# SD_Card.net
KiCad netlist of a schematic drawn in Altium Designer
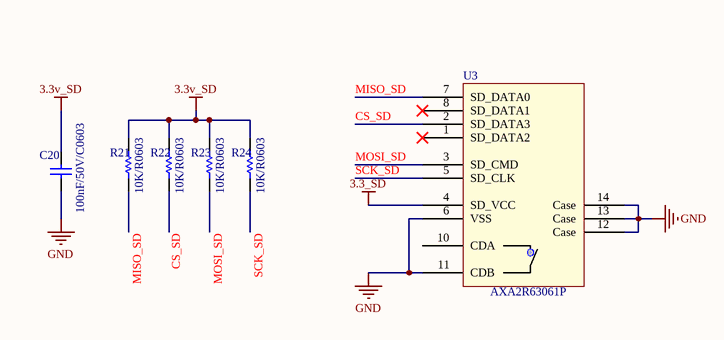
[diagram p0: SD Card.SchDoc]

(export (version "E")
  (design (tool "Eeschema 10.0.6"))
  (components
    (comp (ref "C20")
      (value "100nF/50V/C0603")
      (footprint "Manh_Capacitor:C0603")
      (description "CAP CER 0.1UF 50V 10% X7R 0603")
      (fields
        (field (name "MANUFACTURER") "Murata Electronics North America")
        (field (name "MANUFACTURER PART NUMBER") "GRM188R71H104KA93D")
      )
      (libsource (lib "Manh_Capacitor") (part "0.1uF/50V/C0603/10%"))
    )
    (comp (ref "R21")
      (value "10K/R0603")
      (footprint "Manh_Resistor:R0603")
      (description "RES SMD 10K OHM 1% 1/10W 0603")
      (fields
        (field (name "MANUFACTURER") "Yageo")
        (field (name "MANUFACTURER PART NUMBER") "RC0603FR-0710KL")
      )
      (libsource (lib "Manh_Resistor") (part "10K/R0603/1%"))
    )
    (comp (ref "R22")
      (value "10K/R0603")
      (footprint "Manh_Resistor:R0603")
      (description "RES SMD 10K OHM 1% 1/10W 0603")
      (fields
        (field (name "MANUFACTURER") "Yageo")
        (field (name "MANUFACTURER PART NUMBER") "RC0603FR-0710KL")
      )
      (libsource (lib "Manh_Resistor") (part "10K/R0603/1%"))
    )
    (comp (ref "R23")
      (value "10K/R0603")
      (footprint "Manh_Resistor:R0603")
      (description "RES SMD 10K OHM 1% 1/10W 0603")
      (fields
        (field (name "MANUFACTURER") "Yageo")
        (field (name "MANUFACTURER PART NUMBER") "RC0603FR-0710KL")
      )
      (libsource (lib "Manh_Resistor") (part "10K/R0603/1%"))
    )
    (comp (ref "R24")
      (value "10K/R0603")
      (footprint "Manh_Resistor:R0603")
      (description "RES SMD 10K OHM 1% 1/10W 0603")
      (fields
        (field (name "MANUFACTURER") "Yageo")
        (field (name "MANUFACTURER PART NUMBER") "RC0603FR-0710KL")
      )
      (libsource (lib "Manh_Resistor") (part "10K/R0603/1%"))
    )
    (comp (ref "U3")
      (value "AXA2R63061P")
      (footprint "Manh_Miscellaneous:mini SD card - T-flash")
      (description "CONN SD CARD PUSH-PUSH R/A SMD")
      (fields (field (name "MANUFACTURER") "Panasonic Electric Works"))
      (libsource (lib "Manh_Miscellaneous") (part "MICRO SD CARD P-P R/A SMD"))
    )
  )
  (nets
    (net (code "1") (name "/CS_SD") (class "Default")
      (node (ref "U3") (pin "2") (pinfunction "SD_DATA3_2") (pintype "passive"))
    )
    (net (code "2") (name "/MISO_SD") (class "Default")
      (node (ref "R21") (pin "1") (pinfunction "1_1") (pintype "passive"))
      (node (ref "U3") (pin "7") (pinfunction "SD_DATA0_7") (pintype "passive"))
    )
    (net (code "3") (name "/MOSI_SD") (class "Default")
      (node (ref "R23") (pin "1") (pinfunction "1_1") (pintype "passive"))
      (node (ref "U3") (pin "3") (pinfunction "SD_CMD_3") (pintype "passive"))
    )
    (net (code "4") (name "/SCK_SD") (class "Default")
      (node (ref "R24") (pin "1") (pinfunction "1_1") (pintype "passive"))
      (node (ref "U3") (pin "5") (pinfunction "SD_CLK_5") (pintype "passive"))
    )
    (net (code "5") (name "3.3_SD") (class "Default")
      (node (ref "U3") (pin "4") (pinfunction "SD_VCC_4") (pintype "passive"))
    )
    (net (code "6") (name "3.3v_SD") (class "Default")
      (node (ref "C20") (pin "2") (pinfunction "2_2") (pintype "passive"))
      (node (ref "R21") (pin "2") (pinfunction "2_2") (pintype "passive"))
      (node (ref "R22") (pin "2") (pinfunction "2_2") (pintype "passive"))
      (node (ref "R23") (pin "2") (pinfunction "2_2") (pintype "passive"))
      (node (ref "R24") (pin "2") (pinfunction "2_2") (pintype "passive"))
    )
    (net (code "7") (name "GND") (class "Default")
      (node (ref "C20") (pin "1") (pinfunction "1_1") (pintype "passive"))
      (node (ref "U3") (pin "11") (pinfunction "CDB_11") (pintype "passive"))
      (node (ref "U3") (pin "12") (pinfunction "Case_12") (pintype "passive"))
      (node (ref "U3") (pin "13") (pinfunction "Case_13") (pintype "passive"))
      (node (ref "U3") (pin "14") (pinfunction "Case_14") (pintype "passive"))
      (node (ref "U3") (pin "6") (pinfunction "VSS_6") (pintype "passive"))
    )
    (net (code "8") (name "unconnected-(R22-Pad1)") (class "Default")
      (node (ref "R22") (pin "1") (pinfunction "1_1") (pintype "passive"))
    )
    (net (code "9") (name "unconnected-(U3-CDA-Pad10)") (class "Default")
      (node (ref "U3") (pin "10") (pinfunction "CDA_10") (pintype "passive"))
    )
    (net (code "10") (name "unconnected-(U3-SD_DATA1-Pad8)") (class "Default")
      (node (ref "U3") (pin "8") (pinfunction "SD_DATA1_8") (pintype "passive+no_connect"))
    )
    (net (code "11") (name "unconnected-(U3-SD_DATA2-Pad1)") (class "Default")
      (node (ref "U3") (pin "1") (pinfunction "SD_DATA2_1") (pintype "passive+no_connect"))
    )
  )
)
